# Sensors.net
KiCad netlist of a schematic drawn in Altium Designer
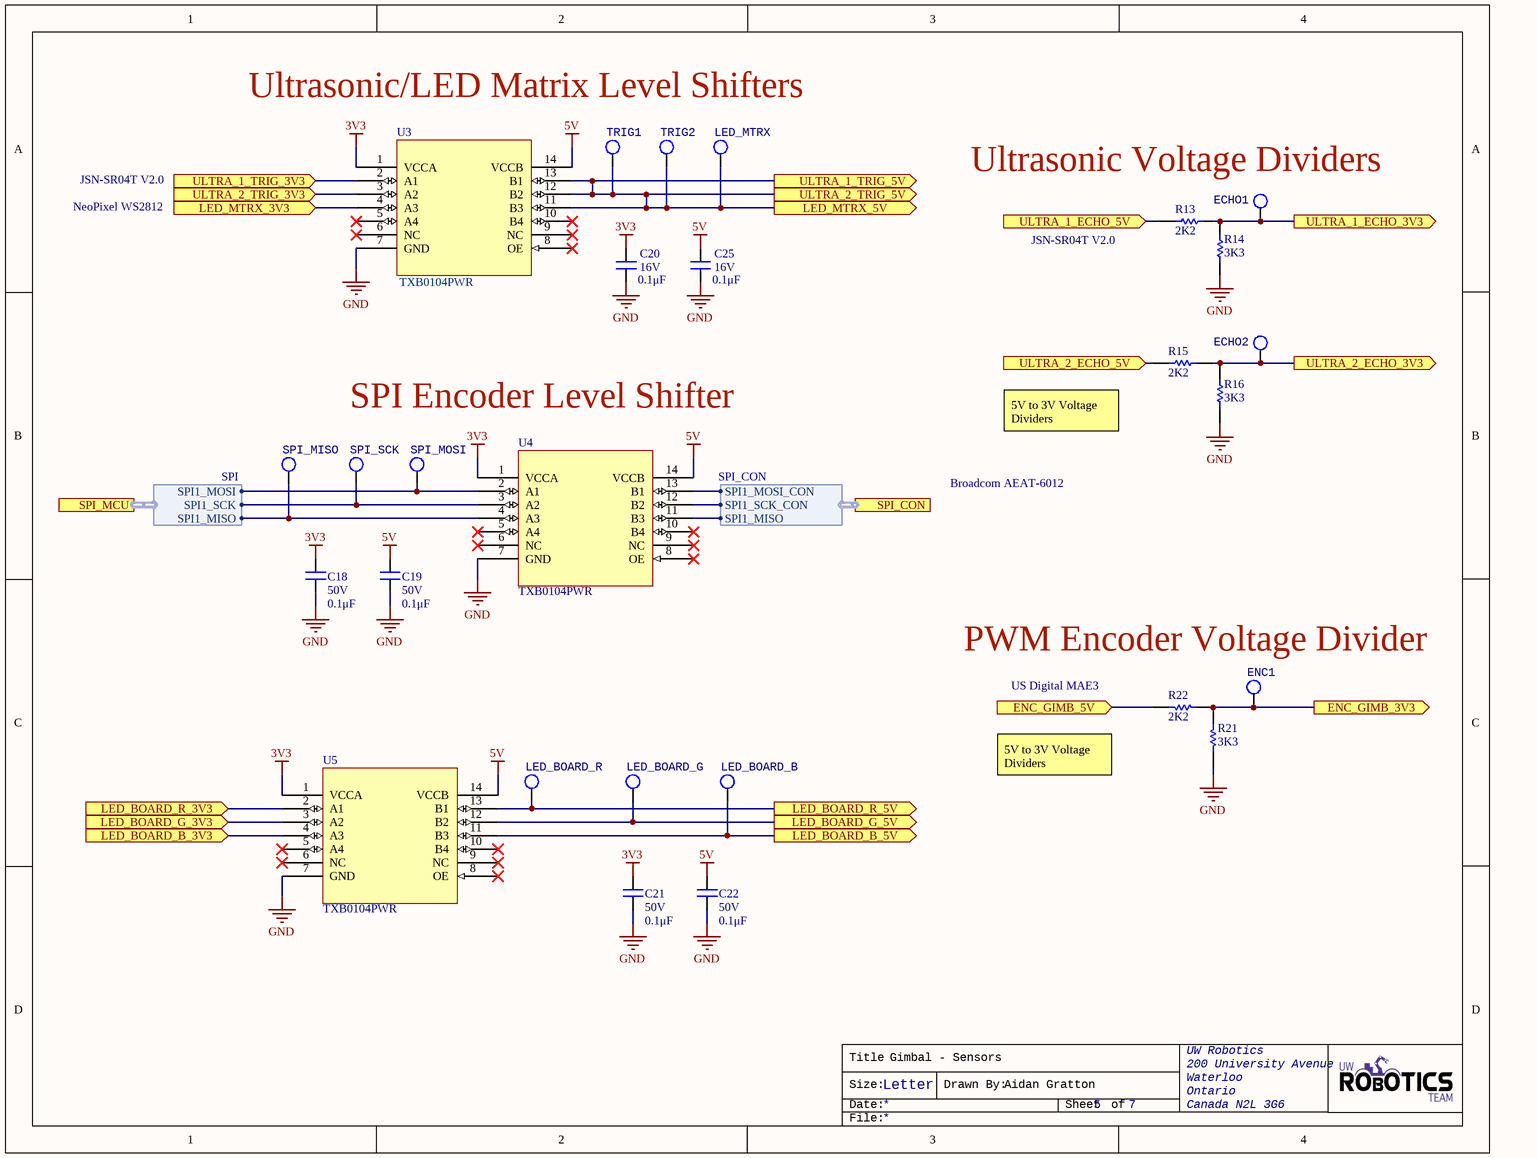
[diagram p0: Sensors.SchDoc]

(export (version "E")
  (design (tool "Eeschema 10.0.6"))
  (components
    (comp (ref "C18")
      (value "0.1μF")
      (footprint "CAPC0603(1608)55_N")
      (description "CAP CER 0.1UF 50V X7R 0603")
      (fields (field (name "VOLTAGE RATING") "50V") (field (name "Comment") "CAP_0.1uF_50V_0603"))
      (libsource (lib "UWRT_Schematic_Library_2020") (part "CAP_0.1uF_50V_0603"))
    )
    (comp (ref "C19")
      (value "0.1μF")
      (footprint "CAPC0603(1608)55_N")
      (description "CAP CER 0.1UF 50V X7R 0603")
      (fields (field (name "VOLTAGE RATING") "50V") (field (name "Comment") "CAP_0.1uF_50V_0603"))
      (libsource (lib "UWRT_Schematic_Library_2020") (part "CAP_0.1uF_50V_0603"))
    )
    (comp (ref "C20")
      (value "0.1μF")
      (footprint "CAPC0603(1608)55_N")
      (description "CAP CER 0.1UF 16V X7R 0603")
      (fields (field (name "VOLTAGE RATING") "16V") (field (name "Comment") "CAP_0.1uF_16V_0603"))
      (libsource (lib "UWRT_Schematic_Library_2020") (part "CAP_0.1uF_16V_0603"))
    )
    (comp (ref "C21")
      (value "0.1μF")
      (footprint "CAPC0603(1608)55_N")
      (description "CAP CER 0.1UF 50V X7R 0603")
      (fields (field (name "VOLTAGE RATING") "50V") (field (name "Comment") "CAP_0.1uF_50V_0603"))
      (libsource (lib "UWRT_Schematic_Library_2020") (part "CAP_0.1uF_50V_0603"))
    )
    (comp (ref "C22")
      (value "0.1μF")
      (footprint "CAPC0603(1608)55_N")
      (description "CAP CER 0.1UF 50V X7R 0603")
      (fields (field (name "VOLTAGE RATING") "50V") (field (name "Comment") "CAP_0.1uF_50V_0603"))
      (libsource (lib "UWRT_Schematic_Library_2020") (part "CAP_0.1uF_50V_0603"))
    )
    (comp (ref "C25")
      (value "0.1μF")
      (footprint "CAPC0603(1608)55_N")
      (description "CAP CER 0.1UF 16V X7R 0603")
      (fields (field (name "VOLTAGE RATING") "16V") (field (name "Comment") "CAP_0.1uF_16V_0603"))
      (libsource (lib "UWRT_Schematic_Library_2020") (part "CAP_0.1uF_16V_0603"))
    )
    (comp (ref "ECHO1")
      (value "TESTPOINT_LOOP")
      (footprint "TESTPOINT_LOOP")
      (description "Loop testpoint through-hole pad")
      (libsource (lib "UWRT_Schematic_Library_2020") (part "TESTPOINT_LOOP"))
    )
    (comp (ref "ECHO2")
      (value "TESTPOINT_LOOP")
      (footprint "TESTPOINT_LOOP")
      (description "Loop testpoint through-hole pad")
      (libsource (lib "UWRT_Schematic_Library_2020") (part "TESTPOINT_LOOP"))
    )
    (comp (ref "ENC1")
      (value "TESTPOINT_LOOP")
      (footprint "TESTPOINT_LOOP")
      (description "Loop testpoint through-hole pad")
      (libsource (lib "UWRT_Schematic_Library_2020") (part "TESTPOINT_LOOP"))
    )
    (comp (ref "LED_BOARD_B")
      (value "TESTPOINT_LOOP")
      (footprint "TESTPOINT_LOOP")
      (description "Loop testpoint through-hole pad")
      (libsource (lib "UWRT_Schematic_Library_2020") (part "TESTPOINT_LOOP"))
    )
    (comp (ref "LED_BOARD_G")
      (value "TESTPOINT_LOOP")
      (footprint "TESTPOINT_LOOP")
      (description "Loop testpoint through-hole pad")
      (libsource (lib "UWRT_Schematic_Library_2020") (part "TESTPOINT_LOOP"))
    )
    (comp (ref "LED_BOARD_R")
      (value "TESTPOINT_LOOP")
      (footprint "TESTPOINT_LOOP")
      (description "Loop testpoint through-hole pad")
      (libsource (lib "UWRT_Schematic_Library_2020") (part "TESTPOINT_LOOP"))
    )
    (comp (ref "LED_MTRX")
      (value "TESTPOINT_LOOP")
      (footprint "TESTPOINT_LOOP")
      (description "Loop testpoint through-hole pad")
      (libsource (lib "UWRT_Schematic_Library_2020") (part "TESTPOINT_LOOP"))
    )
    (comp (ref "R13")
      (value "2K2")
      (footprint "RESC0603(1608)_N")
      (description "RES SMD 2.2K OHM 1% 1/10W 0603")
      (fields (field (name "MANUFACTURER") "Yageo") (field (name "TOLERANCE") "1%"))
      (libsource (lib "UWRT_Schematic_Library_2020") (part "RES_2K2_0603"))
    )
    (comp (ref "R14")
      (value "3K3")
      (footprint "RESC0603(1608)_N")
      (description "RES SMD 3.3K OHM 5% 1/10W 0603")
      (fields (field (name "TOLERANCE") "5%") (field (name "DIGIKEY PART NUMBER") "311-3.3KGRCT-ND"))
      (libsource (lib "UWRT_Schematic_Library_2020") (part "RES_3K3_0603"))
    )
    (comp (ref "R15")
      (value "2K2")
      (footprint "RESC0603(1608)_N")
      (description "RES SMD 2.2K OHM 1% 1/10W 0603")
      (fields (field (name "MANUFACTURER") "Yageo") (field (name "TOLERANCE") "1%"))
      (libsource (lib "UWRT_Schematic_Library_2020") (part "RES_2K2_0603"))
    )
    (comp (ref "R16")
      (value "3K3")
      (footprint "RESC0603(1608)_N")
      (description "RES SMD 3.3K OHM 5% 1/10W 0603")
      (fields (field (name "MANUFACTURER") "Yageo") (field (name "TOLERANCE") "5%"))
      (libsource (lib "") (part "RES_3K3_0603_1"))
    )
    (comp (ref "R21")
      (value "3K3")
      (footprint "RESC0603(1608)_N")
      (description "RES SMD 3.3K OHM 5% 1/10W 0603")
      (fields (field (name "MANUFACTURER") "Yageo") (field (name "TOLERANCE") "5%"))
      (libsource (lib "") (part "RES_3K3_0603_1"))
    )
    (comp (ref "R22")
      (value "2K2")
      (footprint "RESC0603(1608)_N")
      (description "RES SMD 2.2K OHM 1% 1/10W 0603")
      (fields (field (name "MANUFACTURER") "Yageo") (field (name "TOLERANCE") "1%"))
      (libsource (lib "UWRT_Schematic_Library_2020") (part "RES_2K2_0603"))
    )
    (comp (ref "SPI_MISO")
      (value "TESTPOINT_LOOP")
      (footprint "TESTPOINT_LOOP")
      (description "Loop testpoint through-hole pad")
      (libsource (lib "UWRT_Schematic_Library_2020") (part "TESTPOINT_LOOP"))
    )
    (comp (ref "SPI_MOSI")
      (value "TESTPOINT_LOOP")
      (footprint "TESTPOINT_LOOP")
      (description "Loop testpoint through-hole pad")
      (libsource (lib "UWRT_Schematic_Library_2020") (part "TESTPOINT_LOOP"))
    )
    (comp (ref "SPI_SCK")
      (value "TESTPOINT_LOOP")
      (footprint "TESTPOINT_LOOP")
      (description "Loop testpoint through-hole pad")
      (libsource (lib "UWRT_Schematic_Library_2020") (part "TESTPOINT_LOOP"))
    )
    (comp (ref "TRIG1")
      (value "TESTPOINT_LOOP")
      (footprint "TESTPOINT_LOOP")
      (description "Loop testpoint through-hole pad")
      (libsource (lib "UWRT_Schematic_Library_2020") (part "TESTPOINT_LOOP"))
    )
    (comp (ref "TRIG2")
      (value "TESTPOINT_LOOP")
      (footprint "TESTPOINT_LOOP")
      (description "Loop testpoint through-hole pad")
      (libsource (lib "UWRT_Schematic_Library_2020") (part "TESTPOINT_LOOP"))
    )
    (comp (ref "U3")
      (value "TXB0104PWR")
      (footprint "UWRT_Footprint_Library_2020:PW14")
      (fields
        (field (name "GENERIC_PART_NUMBER") "TXB0104")
        (field (name "MANUFACTURER PART NUMBER 1") "TXB0104PWR")
      )
      (libsource (lib "UWRT_Schematic_Library_2020") (part "IC_4CH_LVL_SHIFTER"))
    )
    (comp (ref "U4")
      (value "TXB0104PWR")
      (footprint "UWRT_Footprint_Library_2020:PW14")
      (fields (field (name "GENERIC_PART_NUMBER") "TXB0104"))
      (libsource (lib "UWRT_Schematic_Library_2020") (part "IC_4CH_LVL_SHIFTER"))
    )
    (comp (ref "U5")
      (value "TXB0104PWR")
      (footprint "UWRT_Footprint_Library_2020:PW14")
      (fields (field (name "GENERIC_PART_NUMBER") "TXB0104"))
      (libsource (lib "UWRT_Schematic_Library_2020") (part "IC_4CH_LVL_SHIFTER"))
    )
  )
  (nets
    (net (code "3") (name "/ENC_GIMB_3V3") (class "Default")
      (node (ref "ENC1") (pin "1") (pintype "passive"))
      (node (ref "R21") (pin "1") (pinfunction "1_1") (pintype "passive"))
      (node (ref "R22") (pin "1") (pinfunction "1_1") (pintype "passive"))
    )
    (net (code "4") (name "/ENC_GIMB_5V") (class "Default")
      (node (ref "R22") (pin "2") (pinfunction "2_2") (pintype "passive"))
    )
    (net (code "5") (name "/LED_BOARD_B_3V3") (class "Default")
      (node (ref "U5") (pin "4") (pinfunction "A3_4") (pintype "bidirectional"))
    )
    (net (code "6") (name "/LED_BOARD_B_5V") (class "Default")
      (node (ref "LED_BOARD_B") (pin "1") (pintype "passive"))
      (node (ref "U5") (pin "11") (pinfunction "B3_11") (pintype "bidirectional"))
    )
    (net (code "7") (name "/LED_BOARD_G_3V3") (class "Default")
      (node (ref "U5") (pin "3") (pinfunction "A2_3") (pintype "bidirectional"))
    )
    (net (code "8") (name "/LED_BOARD_G_5V") (class "Default")
      (node (ref "LED_BOARD_G") (pin "1") (pintype "passive"))
      (node (ref "U5") (pin "12") (pinfunction "B2_12") (pintype "bidirectional"))
    )
    (net (code "9") (name "/LED_BOARD_R_3V3") (class "Default")
      (node (ref "U5") (pin "2") (pinfunction "A1_2") (pintype "bidirectional"))
    )
    (net (code "10") (name "/LED_BOARD_R_5V") (class "Default")
      (node (ref "LED_BOARD_R") (pin "1") (pintype "passive"))
      (node (ref "U5") (pin "13") (pinfunction "B1_13") (pintype "bidirectional"))
    )
    (net (code "11") (name "/LED_MTRX_3V3") (class "Default")
      (node (ref "U3") (pin "4") (pinfunction "A3_4") (pintype "bidirectional"))
    )
    (net (code "12") (name "/LED_MTRX_5V") (class "Default")
      (node (ref "LED_MTRX") (pin "1") (pintype "passive"))
      (node (ref "TRIG1") (pin "1") (pintype "passive"))
      (node (ref "TRIG2") (pin "1") (pintype "passive"))
      (node (ref "U3") (pin "11") (pinfunction "B3_11") (pintype "bidirectional"))
      (node (ref "U3") (pin "12") (pinfunction "B2_12") (pintype "bidirectional"))
      (node (ref "U3") (pin "13") (pinfunction "B1_13") (pintype "bidirectional"))
    )
    (net (code "13") (name "/SPI1_MOSI") (class "Default")
      (node (ref "SPI_MOSI") (pin "1") (pintype "passive"))
      (node (ref "U4") (pin "2") (pinfunction "A1_2") (pintype "bidirectional"))
    )
    (net (code "14") (name "/SPI1_MOSI_CON") (class "Default")
      (node (ref "U4") (pin "13") (pinfunction "B1_13") (pintype "bidirectional"))
    )
    (net (code "15") (name "/SPI1_SCK") (class "Default")
      (node (ref "SPI_SCK") (pin "1") (pintype "passive"))
      (node (ref "U4") (pin "3") (pinfunction "A2_3") (pintype "bidirectional"))
    )
    (net (code "16") (name "/SPI1_SCK_CON") (class "Default")
      (node (ref "U4") (pin "12") (pinfunction "B2_12") (pintype "bidirectional"))
    )
    (net (code "17") (name "/ULTRA_1_ECHO_3V3") (class "Default")
      (node (ref "ECHO1") (pin "1") (pintype "passive"))
      (node (ref "R13") (pin "1") (pinfunction "1_1") (pintype "passive"))
      (node (ref "R14") (pin "2") (pinfunction "2_2") (pintype "passive"))
    )
    (net (code "18") (name "/ULTRA_1_ECHO_5V") (class "Default")
      (node (ref "R13") (pin "2") (pinfunction "2_2") (pintype "passive"))
    )
    (net (code "19") (name "/ULTRA_1_TRIG_3V3") (class "Default")
      (node (ref "U3") (pin "2") (pinfunction "A1_2") (pintype "bidirectional"))
    )
    (net (code "20") (name "/ULTRA_2_ECHO_3V3") (class "Default")
      (node (ref "ECHO2") (pin "1") (pintype "passive"))
      (node (ref "R15") (pin "1") (pinfunction "1_1") (pintype "passive"))
      (node (ref "R16") (pin "1") (pinfunction "1_1") (pintype "passive"))
    )
    (net (code "21") (name "/ULTRA_2_ECHO_5V") (class "Default")
      (node (ref "R15") (pin "2") (pinfunction "2_2") (pintype "passive"))
    )
    (net (code "22") (name "/ULTRA_2_TRIG_3V3") (class "Default")
      (node (ref "U3") (pin "3") (pinfunction "A2_3") (pintype "bidirectional"))
    )
    (net (code "25") (name "3V3") (class "Default")
      (node (ref "C18") (pin "2") (pinfunction "2_2") (pintype "passive"))
      (node (ref "C20") (pin "2") (pinfunction "2_2") (pintype "passive"))
      (node (ref "C21") (pin "2") (pinfunction "2_2") (pintype "passive"))
      (node (ref "U3") (pin "1") (pinfunction "VCCA_1") (pintype "power_in"))
      (node (ref "U4") (pin "1") (pinfunction "VCCA_1") (pintype "power_in"))
      (node (ref "U5") (pin "1") (pinfunction "VCCA_1") (pintype "power_in"))
    )
    (net (code "26") (name "5V") (class "Default")
      (node (ref "C19") (pin "2") (pinfunction "2_2") (pintype "passive"))
      (node (ref "C22") (pin "2") (pinfunction "2_2") (pintype "passive"))
      (node (ref "C25") (pin "2") (pinfunction "2_2") (pintype "passive"))
      (node (ref "U3") (pin "14") (pinfunction "VCCB_14") (pintype "power_in"))
      (node (ref "U4") (pin "14") (pinfunction "VCCB_14") (pintype "power_in"))
      (node (ref "U5") (pin "14") (pinfunction "VCCB_14") (pintype "power_in"))
    )
    (net (code "27") (name "GND") (class "Default")
      (node (ref "C18") (pin "1") (pinfunction "1_1") (pintype "passive"))
      (node (ref "C19") (pin "1") (pinfunction "1_1") (pintype "passive"))
      (node (ref "C20") (pin "1") (pinfunction "1_1") (pintype "passive"))
      (node (ref "C21") (pin "1") (pinfunction "1_1") (pintype "passive"))
      (node (ref "C22") (pin "1") (pinfunction "1_1") (pintype "passive"))
      (node (ref "C25") (pin "1") (pinfunction "1_1") (pintype "passive"))
      (node (ref "R14") (pin "1") (pinfunction "1_1") (pintype "passive"))
      (node (ref "R16") (pin "2") (pinfunction "2_2") (pintype "passive"))
      (node (ref "R21") (pin "2") (pinfunction "2_2") (pintype "passive"))
      (node (ref "U3") (pin "7") (pinfunction "GND_7") (pintype "power_in"))
      (node (ref "U4") (pin "7") (pinfunction "GND_7") (pintype "power_in"))
      (node (ref "U5") (pin "7") (pinfunction "GND_7") (pintype "power_in"))
    )
    (net (code "28") (name "Net-(U4-A3)") (class "Default")
      (node (ref "SPI_MISO") (pin "1") (pintype "passive"))
      (node (ref "U4") (pin "4") (pinfunction "A3_4") (pintype "bidirectional"))
    )
    (net (code "29") (name "unconnected-(U3-A4-Pad5)") (class "Default")
      (node (ref "U3") (pin "5") (pinfunction "A4_5") (pintype "bidirectional+no_connect"))
    )
    (net (code "30") (name "unconnected-(U3-B4-Pad10)") (class "Default")
      (node (ref "U3") (pin "10") (pinfunction "B4_10") (pintype "bidirectional+no_connect"))
    )
    (net (code "31") (name "unconnected-(U3-NC-Pad6)") (class "Default")
      (node (ref "U3") (pin "6") (pinfunction "NC_6") (pintype "passive+no_connect"))
    )
    (net (code "32") (name "unconnected-(U3-NC-Pad9)") (class "Default")
      (node (ref "U3") (pin "9") (pinfunction "NC_9") (pintype "passive+no_connect"))
    )
    (net (code "33") (name "unconnected-(U3-OE-Pad8)") (class "Default")
      (node (ref "U3") (pin "8") (pinfunction "OE_8") (pintype "input+no_connect"))
    )
    (net (code "34") (name "unconnected-(U4-A4-Pad5)") (class "Default")
      (node (ref "U4") (pin "5") (pinfunction "A4_5") (pintype "bidirectional+no_connect"))
    )
    (net (code "35") (name "unconnected-(U4-B3-Pad11)") (class "Default")
      (node (ref "U4") (pin "11") (pinfunction "B3_11") (pintype "bidirectional"))
    )
    (net (code "36") (name "unconnected-(U4-B4-Pad10)") (class "Default")
      (node (ref "U4") (pin "10") (pinfunction "B4_10") (pintype "bidirectional+no_connect"))
    )
    (net (code "37") (name "unconnected-(U4-NC-Pad6)") (class "Default")
      (node (ref "U4") (pin "6") (pinfunction "NC_6") (pintype "passive+no_connect"))
    )
    (net (code "38") (name "unconnected-(U4-NC-Pad9)") (class "Default")
      (node (ref "U4") (pin "9") (pinfunction "NC_9") (pintype "passive+no_connect"))
    )
    (net (code "39") (name "unconnected-(U4-OE-Pad8)") (class "Default")
      (node (ref "U4") (pin "8") (pinfunction "OE_8") (pintype "input+no_connect"))
    )
    (net (code "40") (name "unconnected-(U5-A4-Pad5)") (class "Default")
      (node (ref "U5") (pin "5") (pinfunction "A4_5") (pintype "bidirectional+no_connect"))
    )
    (net (code "41") (name "unconnected-(U5-B4-Pad10)") (class "Default")
      (node (ref "U5") (pin "10") (pinfunction "B4_10") (pintype "bidirectional+no_connect"))
    )
    (net (code "42") (name "unconnected-(U5-NC-Pad6)") (class "Default")
      (node (ref "U5") (pin "6") (pinfunction "NC_6") (pintype "passive+no_connect"))
    )
    (net (code "43") (name "unconnected-(U5-NC-Pad9)") (class "Default")
      (node (ref "U5") (pin "9") (pinfunction "NC_9") (pintype "passive+no_connect"))
    )
    (net (code "44") (name "unconnected-(U5-OE-Pad8)") (class "Default")
      (node (ref "U5") (pin "8") (pinfunction "OE_8") (pintype "input+no_connect"))
    )
  )
)
